# Connectors.net
KiCad netlist of a schematic drawn in Altium Designer
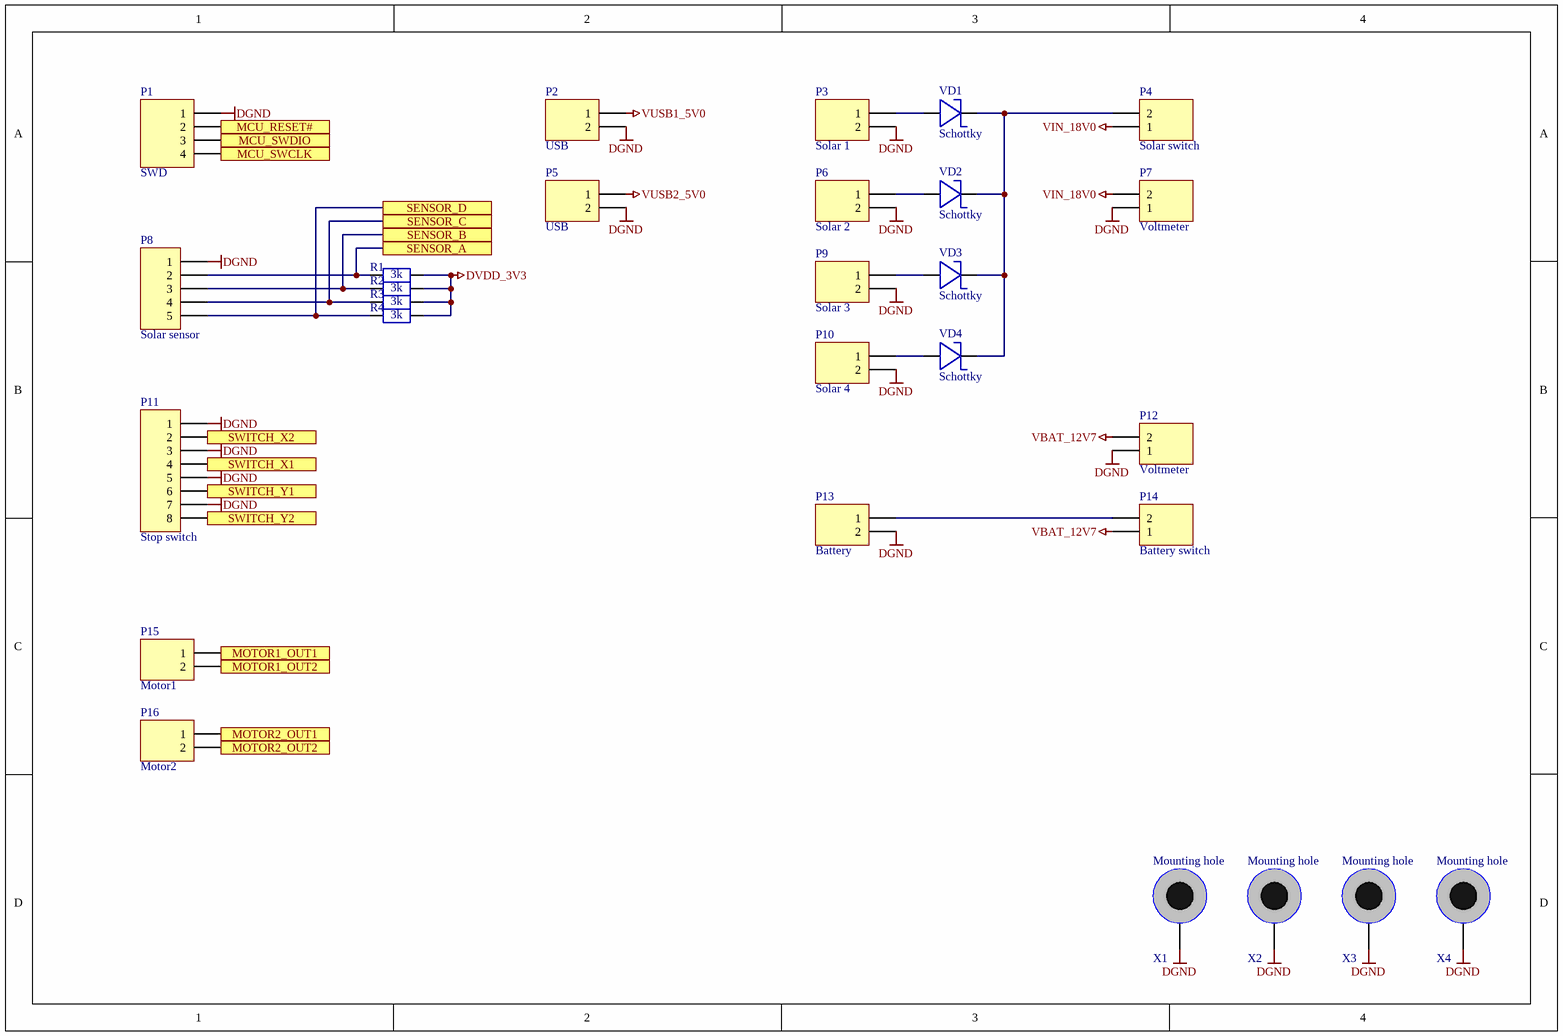
[diagram p0: Connectors.SchDoc]

(export (version "E")
  (design (tool "Eeschema 10.0.6"))
  (components
    (comp (ref "P1")
      (value "SWD")
      (footprint "PLS-4 2.54")
      (description "Header, 4-Pin")
      (fields (field (name "PUBLISHER") "Altium Limited"))
      (libsource (lib "connectors") (part "Header 4"))
    )
    (comp (ref "P2")
      (value "USB")
      (footprint "CWF-2")
      (description "Header, 2-Pin")
      (fields (field (name "PUBLISHER") "Altium Limited"))
      (libsource (lib "") (part "Header 2_1"))
    )
    (comp (ref "P3")
      (value "Solar 1")
      (footprint "CWF-2")
      (description "Header, 2-Pin")
      (fields (field (name "PUBLISHER") "Altium Limited"))
      (libsource (lib "") (part "Header 2_1"))
    )
    (comp (ref "P4")
      (value "Solar switch")
      (footprint "CWF-2")
      (description "Header, 2-Pin")
      (fields (field (name "PUBLISHER") "Altium Limited"))
      (libsource (lib "connectors") (part "Header 2"))
    )
    (comp (ref "P5")
      (value "USB")
      (footprint "CWF-2")
      (description "Header, 2-Pin")
      (fields (field (name "PUBLISHER") "Altium Limited"))
      (libsource (lib "") (part "Header 2_1"))
    )
    (comp (ref "P6")
      (value "Solar 2")
      (footprint "CWF-2")
      (description "Header, 2-Pin")
      (fields (field (name "PUBLISHER") "Altium Limited"))
      (libsource (lib "") (part "Header 2_1"))
    )
    (comp (ref "P7")
      (value "Voltmeter")
      (footprint "CWF-2")
      (description "Header, 2-Pin")
      (fields (field (name "PUBLISHER") "Altium Limited"))
      (libsource (lib "connectors") (part "Header 2"))
    )
    (comp (ref "P8")
      (value "Solar sensor")
      (footprint "HDR1X5")
      (description "Header, 5-Pin")
      (fields (field (name "PUBLISHER") "Altium Limited"))
      (libsource (lib "Miscellaneous Connectors") (part "Header 5"))
    )
    (comp (ref "P9")
      (value "Solar 3")
      (footprint "CWF-2")
      (description "Header, 2-Pin")
      (fields (field (name "PUBLISHER") "Altium Limited"))
      (libsource (lib "") (part "Header 2_1"))
    )
    (comp (ref "P10")
      (value "Solar 4")
      (footprint "CWF-2")
      (description "Header, 2-Pin")
      (fields (field (name "PUBLISHER") "Altium Limited"))
      (libsource (lib "") (part "Header 2_1"))
    )
    (comp (ref "P11")
      (value "Stop switch")
      (footprint "HDR1X8")
      (description "Header, 8-Pin")
      (fields (field (name "PUBLISHER") "Altium Limited"))
      (libsource (lib "Miscellaneous Connectors") (part "Header 8"))
    )
    (comp (ref "P12")
      (value "Voltmeter")
      (footprint "CWF-2")
      (description "Header, 2-Pin")
      (fields (field (name "PUBLISHER") "Altium Limited"))
      (libsource (lib "connectors") (part "Header 2"))
    )
    (comp (ref "P13")
      (value "Battery")
      (footprint "CWF-2")
      (description "Header, 2-Pin")
      (fields (field (name "PUBLISHER") "Altium Limited"))
      (libsource (lib "") (part "Header 2_1"))
    )
    (comp (ref "P14")
      (value "Battery switch")
      (footprint "CWF-2")
      (description "Header, 2-Pin")
      (fields (field (name "PUBLISHER") "Altium Limited"))
      (libsource (lib "connectors") (part "Header 2"))
    )
    (comp (ref "P15")
      (value "Motor1")
      (footprint "CWF-2")
      (description "Header, 2-Pin")
      (fields (field (name "PUBLISHER") "Altium Limited"))
      (libsource (lib "") (part "Header 2_1"))
    )
    (comp (ref "P16")
      (value "Motor2")
      (footprint "CWF-2")
      (description "Header, 2-Pin")
      (fields (field (name "PUBLISHER") "Altium Limited"))
      (libsource (lib "") (part "Header 2_1"))
    )
    (comp (ref "R1")
      (value "3k")
      (footprint "R_0603/1608")
      (description "Resistor")
      (libsource (lib "passive") (part "Resistor"))
    )
    (comp (ref "R2")
      (value "3k")
      (footprint "R_0603/1608")
      (description "Resistor")
      (libsource (lib "passive") (part "Resistor"))
    )
    (comp (ref "R3")
      (value "3k")
      (footprint "R_0603/1608")
      (description "Resistor")
      (libsource (lib "passive") (part "Resistor"))
    )
    (comp (ref "R4")
      (value "3k")
      (footprint "R_0603/1608")
      (description "Resistor")
      (libsource (lib "passive") (part "Resistor"))
    )
    (comp (ref "VD1")
      (value "Schottky")
      (footprint "DO214AC/SMA")
      (description "Schottky diode")
      (libsource (lib "active") (part "Schottky"))
    )
    (comp (ref "VD2")
      (value "Schottky")
      (footprint "DO214AC/SMA")
      (description "Schottky diode")
      (libsource (lib "active") (part "Schottky"))
    )
    (comp (ref "VD3")
      (value "Schottky")
      (footprint "DO214AC/SMA")
      (description "Schottky diode")
      (libsource (lib "active") (part "Schottky"))
    )
    (comp (ref "VD4")
      (value "Schottky")
      (footprint "DO214AC/SMA")
      (description "Schottky diode")
      (libsource (lib "active") (part "Schottky"))
    )
    (comp (ref "X1")
      (value "Mounting hole")
      (footprint "HOLE_M3_D6.0/3.5")
      (description "Hole for screw M3, outline D6")
      (libsource (lib "connectors") (part "Mounting hole"))
    )
    (comp (ref "X2")
      (value "Mounting hole")
      (footprint "HOLE_M3_D6.0/3.5")
      (description "Hole for screw M3, outline D6")
      (libsource (lib "connectors") (part "Mounting hole"))
    )
    (comp (ref "X3")
      (value "Mounting hole")
      (footprint "HOLE_M3_D6.0/3.5")
      (description "Hole for screw M3, outline D6")
      (libsource (lib "connectors") (part "Mounting hole"))
    )
    (comp (ref "X4")
      (value "Mounting hole")
      (footprint "HOLE_M3_D6.0/3.5")
      (description "Hole for screw M3, outline D6")
      (libsource (lib "connectors") (part "Mounting hole"))
    )
  )
  (nets
    (net (code "1") (name "/MCU_RESET#") (class "Default")
      (node (ref "P1") (pin "2") (pinfunction "2_2") (pintype "passive"))
    )
    (net (code "2") (name "/MCU_SWCLK") (class "Default")
      (node (ref "P1") (pin "4") (pinfunction "4_4") (pintype "passive"))
    )
    (net (code "3") (name "/MCU_SWDIO") (class "Default")
      (node (ref "P1") (pin "3") (pinfunction "3_3") (pintype "passive"))
    )
    (net (code "4") (name "/MOTOR1_OUT1") (class "Default")
      (node (ref "P15") (pin "1") (pinfunction "1_1") (pintype "passive"))
    )
    (net (code "5") (name "/MOTOR1_OUT2") (class "Default")
      (node (ref "P15") (pin "2") (pinfunction "2_2") (pintype "passive"))
    )
    (net (code "6") (name "/MOTOR2_OUT1") (class "Default")
      (node (ref "P16") (pin "1") (pinfunction "1_1") (pintype "passive"))
    )
    (net (code "7") (name "/MOTOR2_OUT2") (class "Default")
      (node (ref "P16") (pin "2") (pinfunction "2_2") (pintype "passive"))
    )
    (net (code "8") (name "/SENSOR_A") (class "Default")
      (node (ref "P8") (pin "2") (pinfunction "2_2") (pintype "passive"))
      (node (ref "R1") (pin "2") (pintype "passive"))
    )
    (net (code "9") (name "/SENSOR_B") (class "Default")
      (node (ref "P8") (pin "3") (pinfunction "3_3") (pintype "passive"))
      (node (ref "R2") (pin "2") (pintype "passive"))
    )
    (net (code "10") (name "/SENSOR_C") (class "Default")
      (node (ref "P8") (pin "4") (pinfunction "4_4") (pintype "passive"))
      (node (ref "R3") (pin "2") (pintype "passive"))
    )
    (net (code "11") (name "/SENSOR_D") (class "Default")
      (node (ref "P8") (pin "5") (pinfunction "5_5") (pintype "passive"))
      (node (ref "R4") (pin "2") (pintype "passive"))
    )
    (net (code "12") (name "/SWITCH_X1") (class "Default")
      (node (ref "P11") (pin "4") (pinfunction "4_4") (pintype "passive"))
    )
    (net (code "13") (name "/SWITCH_X2") (class "Default")
      (node (ref "P11") (pin "2") (pinfunction "2_2") (pintype "passive"))
    )
    (net (code "14") (name "/SWITCH_Y1") (class "Default")
      (node (ref "P11") (pin "6") (pinfunction "6_6") (pintype "passive"))
    )
    (net (code "15") (name "/SWITCH_Y2") (class "Default")
      (node (ref "P11") (pin "8") (pinfunction "8_8") (pintype "passive"))
    )
    (net (code "16") (name "DGND") (class "Default")
      (node (ref "P1") (pin "1") (pinfunction "1_1") (pintype "passive"))
      (node (ref "P10") (pin "2") (pinfunction "2_2") (pintype "passive"))
      (node (ref "P11") (pin "1") (pinfunction "1_1") (pintype "passive"))
      (node (ref "P11") (pin "3") (pinfunction "3_3") (pintype "passive"))
      (node (ref "P11") (pin "5") (pinfunction "5_5") (pintype "passive"))
      (node (ref "P11") (pin "7") (pinfunction "7_7") (pintype "passive"))
      (node (ref "P12") (pin "1") (pinfunction "1_1") (pintype "passive"))
      (node (ref "P13") (pin "2") (pinfunction "2_2") (pintype "passive"))
      (node (ref "P2") (pin "2") (pinfunction "2_2") (pintype "passive"))
      (node (ref "P3") (pin "2") (pinfunction "2_2") (pintype "passive"))
      (node (ref "P5") (pin "2") (pinfunction "2_2") (pintype "passive"))
      (node (ref "P6") (pin "2") (pinfunction "2_2") (pintype "passive"))
      (node (ref "P7") (pin "1") (pinfunction "1_1") (pintype "passive"))
      (node (ref "P8") (pin "1") (pinfunction "1_1") (pintype "passive"))
      (node (ref "P9") (pin "2") (pinfunction "2_2") (pintype "passive"))
      (node (ref "X1") (pin "1") (pintype "passive"))
      (node (ref "X2") (pin "1") (pintype "passive"))
      (node (ref "X3") (pin "1") (pintype "passive"))
      (node (ref "X4") (pin "1") (pintype "passive"))
    )
    (net (code "17") (name "DVDD_3V3") (class "Default")
      (node (ref "R1") (pin "1") (pintype "passive"))
      (node (ref "R2") (pin "1") (pintype "passive"))
      (node (ref "R3") (pin "1") (pintype "passive"))
      (node (ref "R4") (pin "1") (pintype "passive"))
    )
    (net (code "18") (name "Net-(P3-Pad1)") (class "Default")
      (node (ref "P3") (pin "1") (pinfunction "1_1") (pintype "passive"))
      (node (ref "VD1") (pin "1") (pinfunction "1_1") (pintype "passive"))
    )
    (net (code "19") (name "Net-(P4-Pad2)") (class "Default")
      (node (ref "P4") (pin "2") (pinfunction "2_2") (pintype "passive"))
      (node (ref "VD1") (pin "2") (pinfunction "2_2") (pintype "passive"))
      (node (ref "VD2") (pin "2") (pinfunction "2_2") (pintype "passive"))
      (node (ref "VD3") (pin "2") (pinfunction "2_2") (pintype "passive"))
      (node (ref "VD4") (pin "2") (pinfunction "2_2") (pintype "passive"))
    )
    (net (code "20") (name "Net-(P6-Pad1)") (class "Default")
      (node (ref "P6") (pin "1") (pinfunction "1_1") (pintype "passive"))
      (node (ref "VD2") (pin "1") (pinfunction "1_1") (pintype "passive"))
    )
    (net (code "21") (name "Net-(P9-Pad1)") (class "Default")
      (node (ref "P9") (pin "1") (pinfunction "1_1") (pintype "passive"))
      (node (ref "VD3") (pin "1") (pinfunction "1_1") (pintype "passive"))
    )
    (net (code "22") (name "Net-(P10-Pad1)") (class "Default")
      (node (ref "P10") (pin "1") (pinfunction "1_1") (pintype "passive"))
      (node (ref "VD4") (pin "1") (pinfunction "1_1") (pintype "passive"))
    )
    (net (code "23") (name "Net-(P13-Pad1)") (class "Default")
      (node (ref "P13") (pin "1") (pinfunction "1_1") (pintype "passive"))
      (node (ref "P14") (pin "2") (pinfunction "2_2") (pintype "passive"))
    )
    (net (code "24") (name "VBAT_12V7") (class "Default")
      (node (ref "P12") (pin "2") (pinfunction "2_2") (pintype "passive"))
      (node (ref "P14") (pin "1") (pinfunction "1_1") (pintype "passive"))
    )
    (net (code "25") (name "VIN_18V0") (class "Default")
      (node (ref "P4") (pin "1") (pinfunction "1_1") (pintype "passive"))
      (node (ref "P7") (pin "2") (pinfunction "2_2") (pintype "passive"))
    )
    (net (code "26") (name "VUSB1_5V0") (class "Default")
      (node (ref "P2") (pin "1") (pinfunction "1_1") (pintype "passive"))
    )
    (net (code "27") (name "VUSB2_5V0") (class "Default")
      (node (ref "P5") (pin "1") (pinfunction "1_1") (pintype "passive"))
    )
  )
)
